# 3_3V_Regulator.net
KiCad netlist of a schematic drawn in Altium Designer
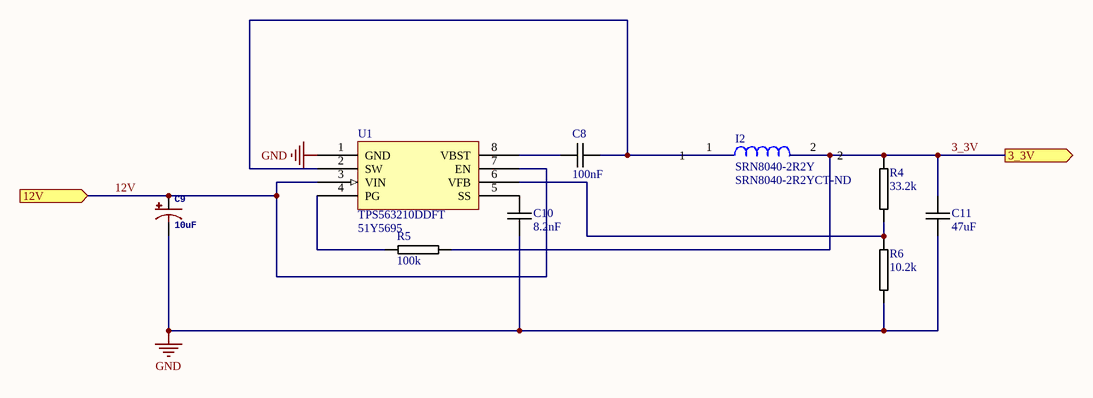
[diagram p0: 3_3V Regulator.SchDoc]

(export (version "E")
  (design (tool "Eeschema 10.0.6"))
  (components
    (comp (ref "C8")
      (value "100nF")
      (footprint "0805C-TBD")
      (description "CAPACITOR 0805 CERAMIC")
      (fields
        (field (name "MANUFACTURER PART NUMBER") "ECJ-1VB0J225K")
        (field (name "MANUFACTURER") "Panasonic - ECG")
      )
      (libsource (lib "vh_altium_library") (part "0603C-2U2-6V3-X5R-PAN"))
    )
    (comp (ref "C9")
      (value "10uF")
      (footprint "EIA3216")
      (libsource (lib "SparkFun-Retired") (part "10UF-TANT"))
    )
    (comp (ref "C10")
      (value "8.2nF")
      (footprint "0603C-GENERIC")
      (description "CAPACITOR 0603 CERAMIC")
      (libsource (lib "vh_altium_library") (part "0603C-000"))
    )
    (comp (ref "C11")
      (value "47uF")
      (footprint "0805C-TBD")
      (description "CAPACITOR 0805 CERAMIC")
      (fields
        (field (name "MANUFACTURER PART NUMBER") "ECJ-1VB0J225K")
        (field (name "MANUFACTURER") "Panasonic - ECG")
      )
      (libsource (lib "vh_altium_library") (part "0603C-2U2-6V3-X5R-PAN"))
    )
    (comp (ref "I2")
      (value "SRN8040-2R2Y")
      (footprint "SRN8040")
      (description "FIXED IND 2.2UH 6.3A 13 MOHM SMD")
      (fields
        (field (name "MANUFACTURER") "Bourns Inc.")
        (field (name "TOLERANCE") "±30%")
        (field (name "SUPPLIER PART NUMBER 1") "SRN8040-2R2YCT-ND")
      )
      (libsource (lib "Digi_Key") (part "SRN8040-2R2Y"))
    )
    (comp (ref "R4")
      (value "33.2k")
      (footprint "0402R-TBD")
      (description "RESISTOR 0402 VALUE TO BE DETERMINED")
      (libsource (lib "vh_altium_library") (part "0402R-TBD"))
    )
    (comp (ref "R5")
      (value "100k")
      (footprint "0402R-TBD")
      (description "RESISTOR 0402 VALUE TO BE DETERMINED")
      (libsource (lib "vh_altium_library") (part "0402R-TBD"))
    )
    (comp (ref "R6")
      (value "10.2k")
      (footprint "0402R-TBD")
      (description "RESISTOR 0402 VALUE TO BE DETERMINED")
      (libsource (lib "vh_altium_library") (part "0402R-TBD"))
    )
    (comp (ref "U1")
      (value "TPS563210DDFT")
      (footprint "vh_altium_library:SOT23-8")
      (description "TEXAS INSTRUMENTS - TPS563210DDFT - DC/DC CONV, SYNC BUCK, 650KHZ, SOT-23-8")
      (fields
        (field (name "MANUFACTURER") "TEXAS INSTRUMENTS")
        (field (name "SUPPLIER PART NUMBER 1") "51Y5695")
      )
      (libsource (lib "Digi_Key") (part "TPS563210DDFT"))
    )
  )
  (nets
    (net (code "1") (name "/3_3V") (class "Default")
      (node (ref "C11") (pin "2") (pintype "passive"))
      (node (ref "I2") (pin "2") (pinfunction "2_2") (pintype "passive"))
      (node (ref "R4") (pin "1") (pintype "passive"))
      (node (ref "R5") (pin "2") (pintype "passive"))
    )
    (net (code "2") (name "/12V") (class "Default")
      (node (ref "C9") (pin "A") (pinfunction "+_A") (pintype "passive"))
      (node (ref "U1") (pin "3") (pinfunction "VIN_3") (pintype "input"))
      (node (ref "U1") (pin "7") (pinfunction "EN_7") (pintype "passive"))
    )
    (net (code "3") (name "GND") (class "Default")
      (node (ref "C10") (pin "2") (pintype "passive"))
      (node (ref "C11") (pin "1") (pintype "passive"))
      (node (ref "C9") (pin "C") (pinfunction "-_C") (pintype "passive"))
      (node (ref "R6") (pin "2") (pintype "passive"))
      (node (ref "U1") (pin "1") (pinfunction "GND_1") (pintype "passive"))
    )
    (net (code "4") (name "Net-(U1-PG)") (class "Default")
      (node (ref "R5") (pin "1") (pintype "passive"))
      (node (ref "U1") (pin "4") (pinfunction "PG_4") (pintype "passive"))
    )
    (net (code "5") (name "Net-(U1-SS)") (class "Default")
      (node (ref "C10") (pin "1") (pintype "passive"))
      (node (ref "U1") (pin "5") (pinfunction "SS_5") (pintype "passive"))
    )
    (net (code "6") (name "Net-(U1-SW)") (class "Default")
      (node (ref "C8") (pin "2") (pintype "passive"))
      (node (ref "I2") (pin "1") (pinfunction "1_1") (pintype "passive"))
      (node (ref "U1") (pin "2") (pinfunction "SW_2") (pintype "passive"))
    )
    (net (code "7") (name "Net-(U1-VBST)") (class "Default")
      (node (ref "C8") (pin "1") (pintype "passive"))
      (node (ref "U1") (pin "8") (pinfunction "VBST_8") (pintype "passive"))
    )
    (net (code "8") (name "Net-(U1-VFB)") (class "Default")
      (node (ref "R4") (pin "2") (pintype "passive"))
      (node (ref "R6") (pin "1") (pintype "passive"))
      (node (ref "U1") (pin "6") (pinfunction "VFB_6") (pintype "passive"))
    )
  )
)
